# SCH_USB-Hub_2024-10-09.net
KiCad netlist of a schematic drawn in EasyEDA
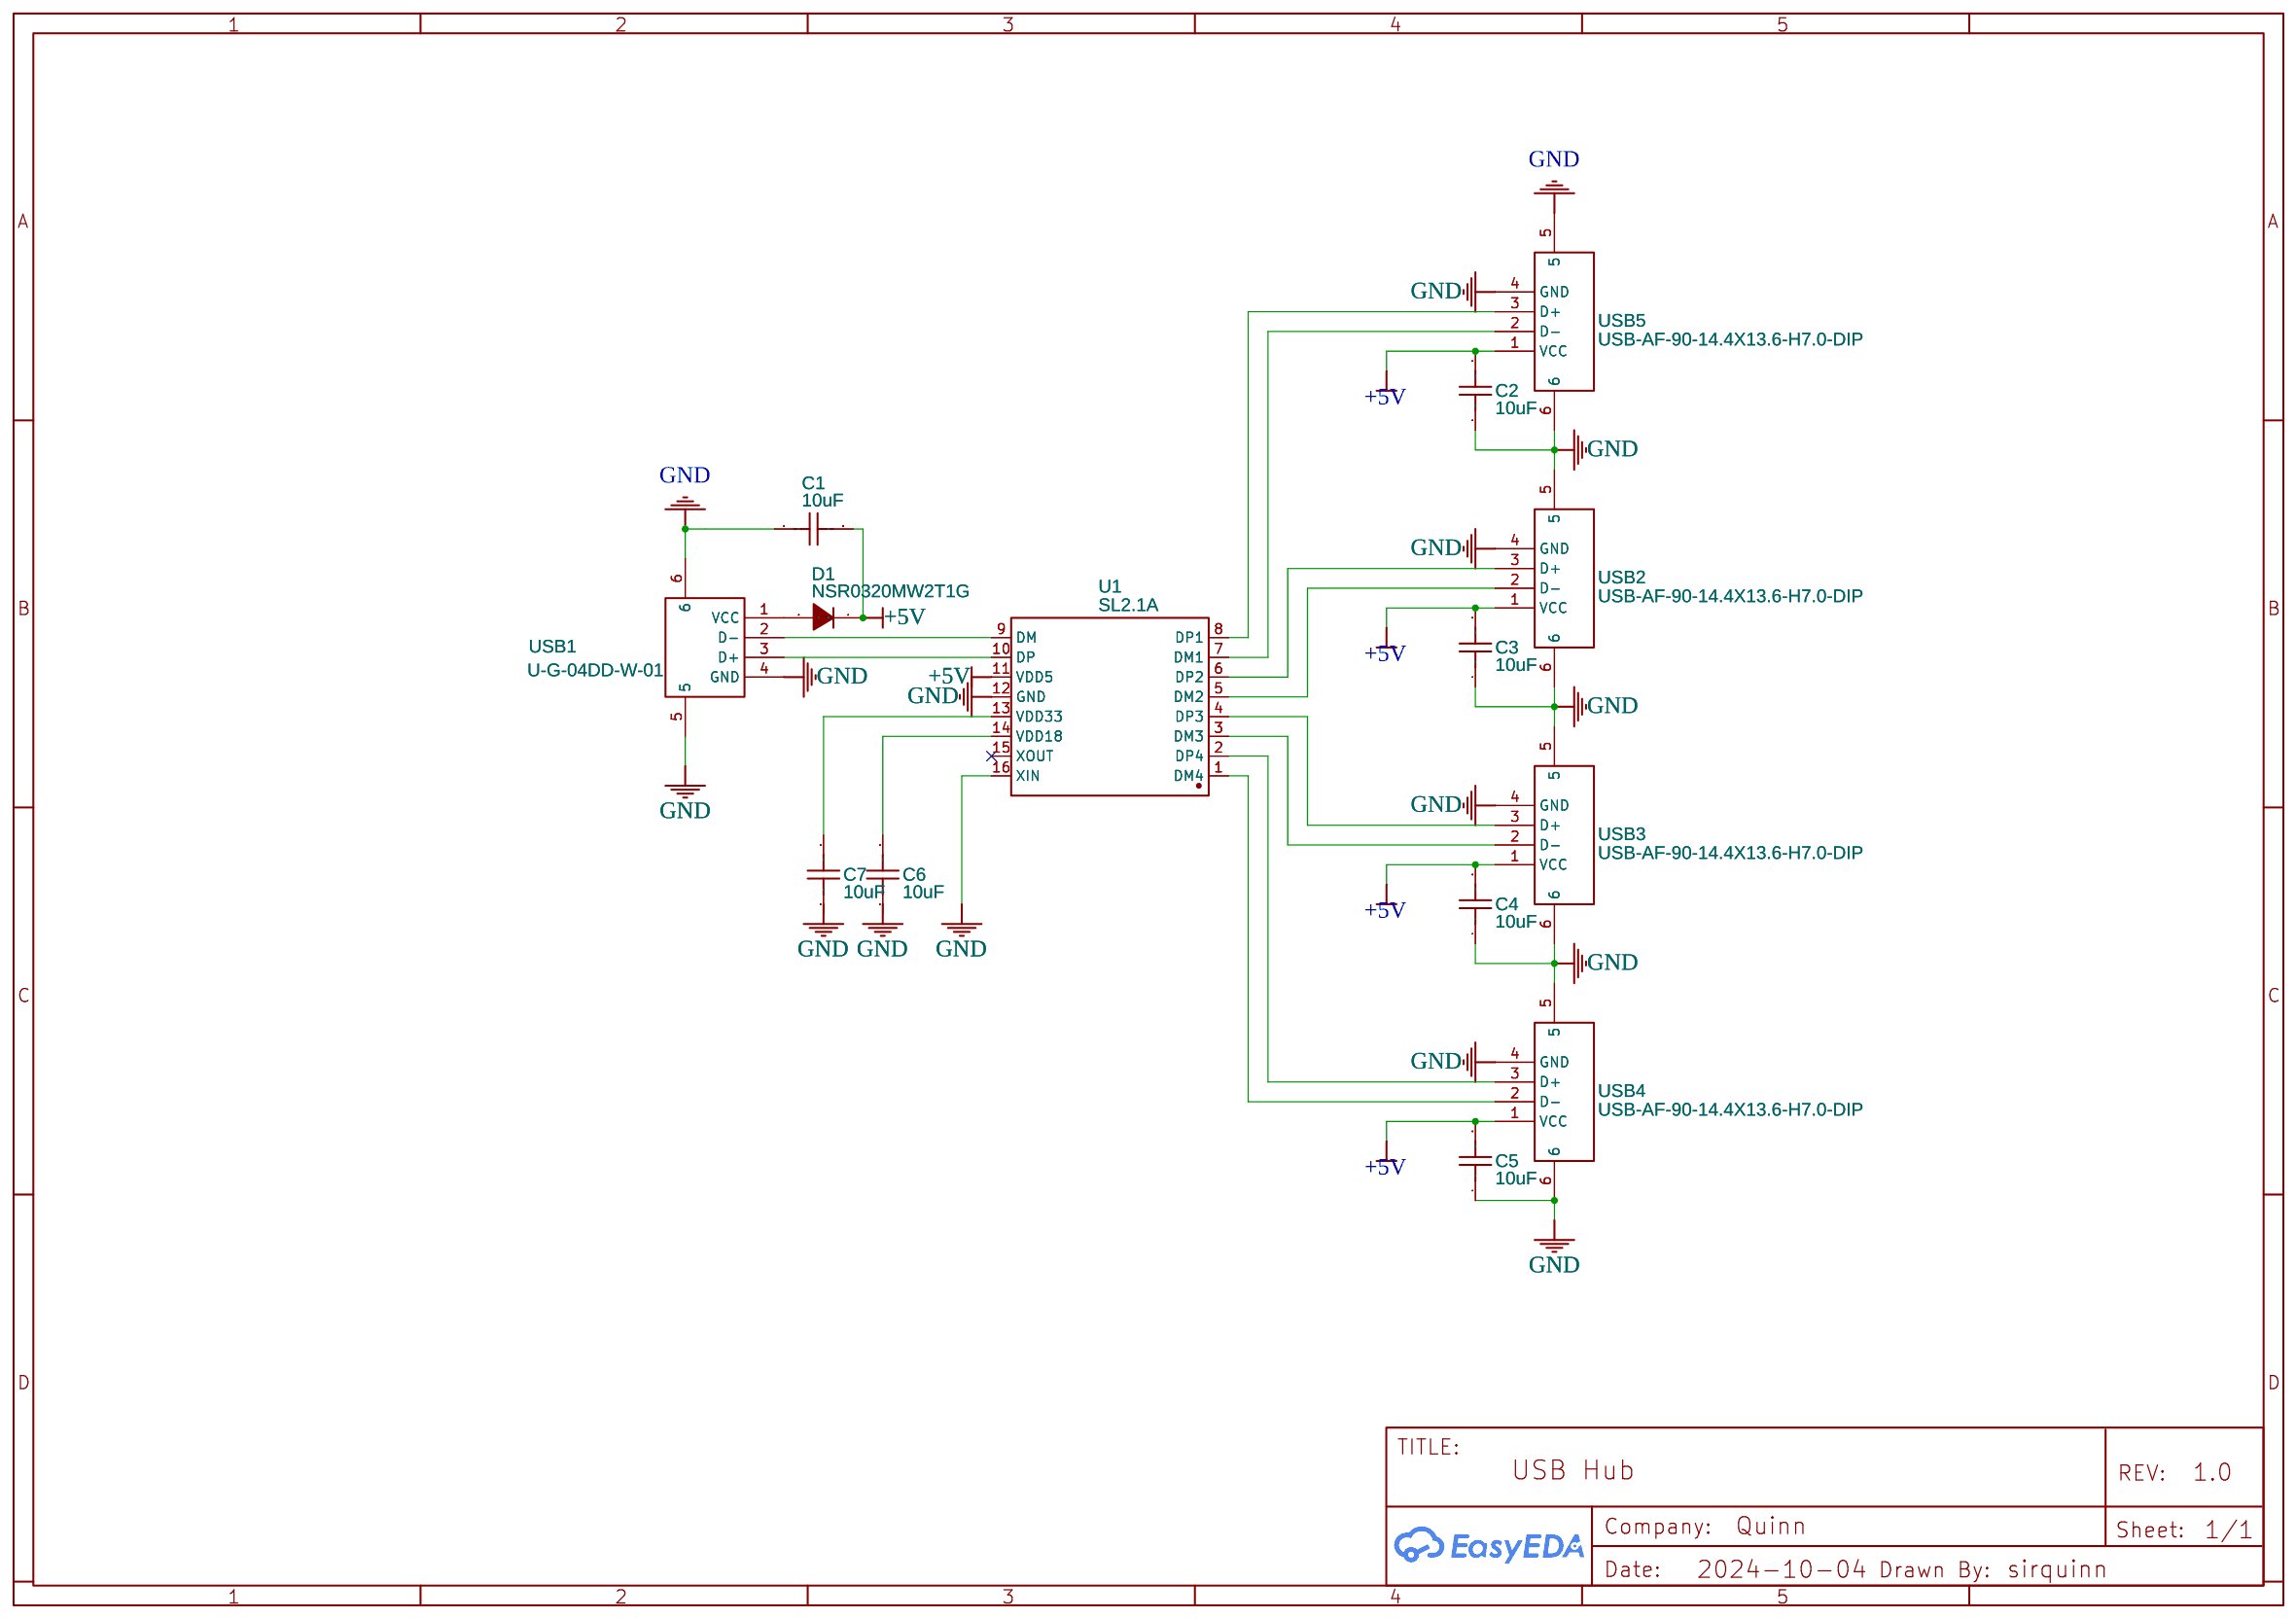
[diagram p0: schematic sheet]

(export (version "E")
  (design (tool "Eeschema 10.0.6"))
  (components
    (comp (ref "C1")
      (value "10uF")
      (fields
        (field (name "Manufacturer Part") "CL10A106KP8NNNC")
        (field (name "Manufacturer") "SAMSUNG(三星)")
      )
      (libsource (lib "") (part "CL10A106KP8NNNC_1"))
    )
    (comp (ref "C2")
      (value "10uF")
      (fields
        (field (name "Manufacturer Part") "CL10A106KP8NNNC")
        (field (name "Manufacturer") "SAMSUNG(三星)")
      )
      (libsource (lib "") (part "CL10A106KP8NNNC"))
    )
    (comp (ref "C3")
      (value "10uF")
      (fields
        (field (name "Manufacturer Part") "CL10A106KP8NNNC")
        (field (name "Manufacturer") "SAMSUNG(三星)")
      )
      (libsource (lib "") (part "CL10A106KP8NNNC"))
    )
    (comp (ref "C4")
      (value "10uF")
      (fields
        (field (name "Manufacturer Part") "CL10A106KP8NNNC")
        (field (name "Manufacturer") "SAMSUNG(三星)")
      )
      (libsource (lib "") (part "CL10A106KP8NNNC"))
    )
    (comp (ref "C5")
      (value "10uF")
      (fields
        (field (name "Manufacturer Part") "CL10A106KP8NNNC")
        (field (name "Manufacturer") "SAMSUNG(三星)")
      )
      (libsource (lib "") (part "CL10A106KP8NNNC"))
    )
    (comp (ref "C6")
      (value "10uF")
      (fields
        (field (name "Manufacturer Part") "CL10A106KP8NNNC")
        (field (name "Manufacturer") "SAMSUNG(三星)")
      )
      (libsource (lib "") (part "CL10A106KP8NNNC"))
    )
    (comp (ref "C7")
      (value "10uF")
      (fields
        (field (name "Manufacturer Part") "CL10A106KP8NNNC")
        (field (name "Manufacturer") "SAMSUNG(三星)")
      )
      (libsource (lib "") (part "CL10A106KP8NNNC"))
    )
    (comp (ref "D1")
      (value "NSR0320MW2T1G")
      (fields (field (name "Manufacturer") "onsemi(安森美)"))
      (libsource (lib "") (part "NSR0320MW2T1G"))
    )
    (comp (ref "U1")
      (value "SL2.1A")
      (fields (field (name "Manufacturer") "CoreChips(和芯润德)"))
      (libsource (lib "") (part "SL2.1A"))
    )
    (comp (ref "USB1")
      (value "U-G-04DD-W-01")
      (fields (field (name "Manufacturer Part") "U-G-O4DD-W-1") (field (name "Manufacturer") "韩国韩荣"))
      (libsource (lib "") (part "U-G-04DD-W-01"))
    )
    (comp (ref "USB2")
      (value "USB-AF-90-14.4X13.6-H7.0-DIP")
      (fields (field (name "Manufacturer Part") "903-131A1011D10100") (field (name "Manufacturer") "精拓金"))
      (libsource (lib "") (part "USB-AF-90-14.4X13.6-H7.0-DIP"))
    )
    (comp (ref "USB3")
      (value "USB-AF-90-14.4X13.6-H7.0-DIP")
      (fields (field (name "Manufacturer Part") "903-131A1011D10100") (field (name "Manufacturer") "精拓金"))
      (libsource (lib "") (part "USB-AF-90-14.4X13.6-H7.0-DIP"))
    )
    (comp (ref "USB4")
      (value "USB-AF-90-14.4X13.6-H7.0-DIP")
      (fields (field (name "Manufacturer Part") "903-131A1011D10100") (field (name "Manufacturer") "精拓金"))
      (libsource (lib "") (part "USB-AF-90-14.4X13.6-H7.0-DIP"))
    )
    (comp (ref "USB5")
      (value "USB-AF-90-14.4X13.6-H7.0-DIP")
      (fields (field (name "Manufacturer Part") "903-131A1011D10100") (field (name "Manufacturer") "精拓金"))
      (libsource (lib "") (part "USB-AF-90-14.4X13.6-H7.0-DIP"))
    )
  )
  (nets
    (net (code "1") (name "+5V") (class "Default")
      (node (ref "C1") (pin "2") (pinfunction "2_2") (pintype "unspecified"))
      (node (ref "C2") (pin "2") (pinfunction "2_2") (pintype "unspecified"))
      (node (ref "C3") (pin "2") (pinfunction "2_2") (pintype "unspecified"))
      (node (ref "C4") (pin "2") (pinfunction "2_2") (pintype "unspecified"))
      (node (ref "C5") (pin "2") (pinfunction "2_2") (pintype "unspecified"))
      (node (ref "D1") (pin "1") (pinfunction "C_1") (pintype "unspecified"))
      (node (ref "U1") (pin "11") (pinfunction "VDD5_11") (pintype "unspecified"))
      (node (ref "USB2") (pin "1") (pinfunction "VCC_1") (pintype "unspecified"))
      (node (ref "USB3") (pin "1") (pinfunction "VCC_1") (pintype "unspecified"))
      (node (ref "USB4") (pin "1") (pinfunction "VCC_1") (pintype "unspecified"))
      (node (ref "USB5") (pin "1") (pinfunction "VCC_1") (pintype "unspecified"))
    )
    (net (code "2") (name "GND") (class "Default")
      (node (ref "C1") (pin "1") (pinfunction "1_1") (pintype "unspecified"))
      (node (ref "C2") (pin "1") (pinfunction "1_1") (pintype "unspecified"))
      (node (ref "C3") (pin "1") (pinfunction "1_1") (pintype "unspecified"))
      (node (ref "C4") (pin "1") (pinfunction "1_1") (pintype "unspecified"))
      (node (ref "C5") (pin "1") (pinfunction "1_1") (pintype "unspecified"))
      (node (ref "C6") (pin "1") (pinfunction "1_1") (pintype "unspecified"))
      (node (ref "C7") (pin "1") (pinfunction "1_1") (pintype "unspecified"))
      (node (ref "U1") (pin "12") (pinfunction "GND_12") (pintype "unspecified"))
      (node (ref "U1") (pin "16") (pinfunction "XIN_16") (pintype "unspecified"))
      (node (ref "USB1") (pin "4") (pinfunction "GND_4") (pintype "unspecified"))
      (node (ref "USB1") (pin "5") (pinfunction "5_5") (pintype "unspecified"))
      (node (ref "USB1") (pin "6") (pinfunction "6_6") (pintype "unspecified"))
      (node (ref "USB2") (pin "4") (pinfunction "GND_4") (pintype "unspecified"))
      (node (ref "USB2") (pin "5") (pinfunction "5_5") (pintype "unspecified"))
      (node (ref "USB2") (pin "6") (pinfunction "6_6") (pintype "unspecified"))
      (node (ref "USB3") (pin "4") (pinfunction "GND_4") (pintype "unspecified"))
      (node (ref "USB3") (pin "5") (pinfunction "5_5") (pintype "unspecified"))
      (node (ref "USB3") (pin "6") (pinfunction "6_6") (pintype "unspecified"))
      (node (ref "USB4") (pin "4") (pinfunction "GND_4") (pintype "unspecified"))
      (node (ref "USB4") (pin "5") (pinfunction "5_5") (pintype "unspecified"))
      (node (ref "USB4") (pin "6") (pinfunction "6_6") (pintype "unspecified"))
      (node (ref "USB5") (pin "4") (pinfunction "GND_4") (pintype "unspecified"))
      (node (ref "USB5") (pin "5") (pinfunction "5_5") (pintype "unspecified"))
      (node (ref "USB5") (pin "6") (pinfunction "6_6") (pintype "unspecified"))
    )
    (net (code "3") (name "Net-(D1-A)") (class "Default")
      (node (ref "D1") (pin "2") (pinfunction "A_2") (pintype "unspecified"))
      (node (ref "USB1") (pin "1") (pinfunction "VCC_1") (pintype "unspecified"))
    )
    (net (code "4") (name "Net-(U1-DM)") (class "Default")
      (node (ref "U1") (pin "9") (pinfunction "DM_9") (pintype "unspecified"))
      (node (ref "USB1") (pin "2") (pinfunction "D-_2") (pintype "unspecified"))
    )
    (net (code "5") (name "Net-(U1-DM1)") (class "Default")
      (node (ref "U1") (pin "7") (pinfunction "DM1_7") (pintype "unspecified"))
      (node (ref "USB5") (pin "2") (pinfunction "D-_2") (pintype "unspecified"))
    )
    (net (code "6") (name "Net-(U1-DM2)") (class "Default")
      (node (ref "U1") (pin "5") (pinfunction "DM2_5") (pintype "unspecified"))
      (node (ref "USB2") (pin "2") (pinfunction "D-_2") (pintype "unspecified"))
    )
    (net (code "7") (name "Net-(U1-DM3)") (class "Default")
      (node (ref "U1") (pin "3") (pinfunction "DM3_3") (pintype "unspecified"))
      (node (ref "USB3") (pin "2") (pinfunction "D-_2") (pintype "unspecified"))
    )
    (net (code "8") (name "Net-(U1-DM4)") (class "Default")
      (node (ref "U1") (pin "1") (pinfunction "DM4_1") (pintype "unspecified"))
      (node (ref "USB4") (pin "2") (pinfunction "D-_2") (pintype "unspecified"))
    )
    (net (code "9") (name "Net-(U1-DP)") (class "Default")
      (node (ref "U1") (pin "10") (pinfunction "DP_10") (pintype "unspecified"))
      (node (ref "USB1") (pin "3") (pinfunction "D+_3") (pintype "unspecified"))
    )
    (net (code "10") (name "Net-(U1-DP1)") (class "Default")
      (node (ref "U1") (pin "8") (pinfunction "DP1_8") (pintype "unspecified"))
      (node (ref "USB5") (pin "3") (pinfunction "D+_3") (pintype "unspecified"))
    )
    (net (code "11") (name "Net-(U1-DP2)") (class "Default")
      (node (ref "U1") (pin "6") (pinfunction "DP2_6") (pintype "unspecified"))
      (node (ref "USB2") (pin "3") (pinfunction "D+_3") (pintype "unspecified"))
    )
    (net (code "12") (name "Net-(U1-DP3)") (class "Default")
      (node (ref "U1") (pin "4") (pinfunction "DP3_4") (pintype "unspecified"))
      (node (ref "USB3") (pin "3") (pinfunction "D+_3") (pintype "unspecified"))
    )
    (net (code "13") (name "Net-(U1-DP4)") (class "Default")
      (node (ref "U1") (pin "2") (pinfunction "DP4_2") (pintype "unspecified"))
      (node (ref "USB4") (pin "3") (pinfunction "D+_3") (pintype "unspecified"))
    )
    (net (code "14") (name "Net-(U1-VDD18)") (class "Default")
      (node (ref "C6") (pin "2") (pinfunction "2_2") (pintype "unspecified"))
      (node (ref "U1") (pin "14") (pinfunction "VDD18_14") (pintype "unspecified"))
    )
    (net (code "15") (name "Net-(U1-VDD33)") (class "Default")
      (node (ref "C7") (pin "2") (pinfunction "2_2") (pintype "unspecified"))
      (node (ref "U1") (pin "13") (pinfunction "VDD33_13") (pintype "unspecified"))
    )
    (net (code "16") (name "unconnected-(U1-XOUT-Pad15)") (class "Default")
      (node (ref "U1") (pin "15") (pinfunction "XOUT_15") (pintype "unspecified+no_connect"))
    )
  )
)
